# Dock_P1RB.net
KiCad netlist of a schematic drawn in EAGLE
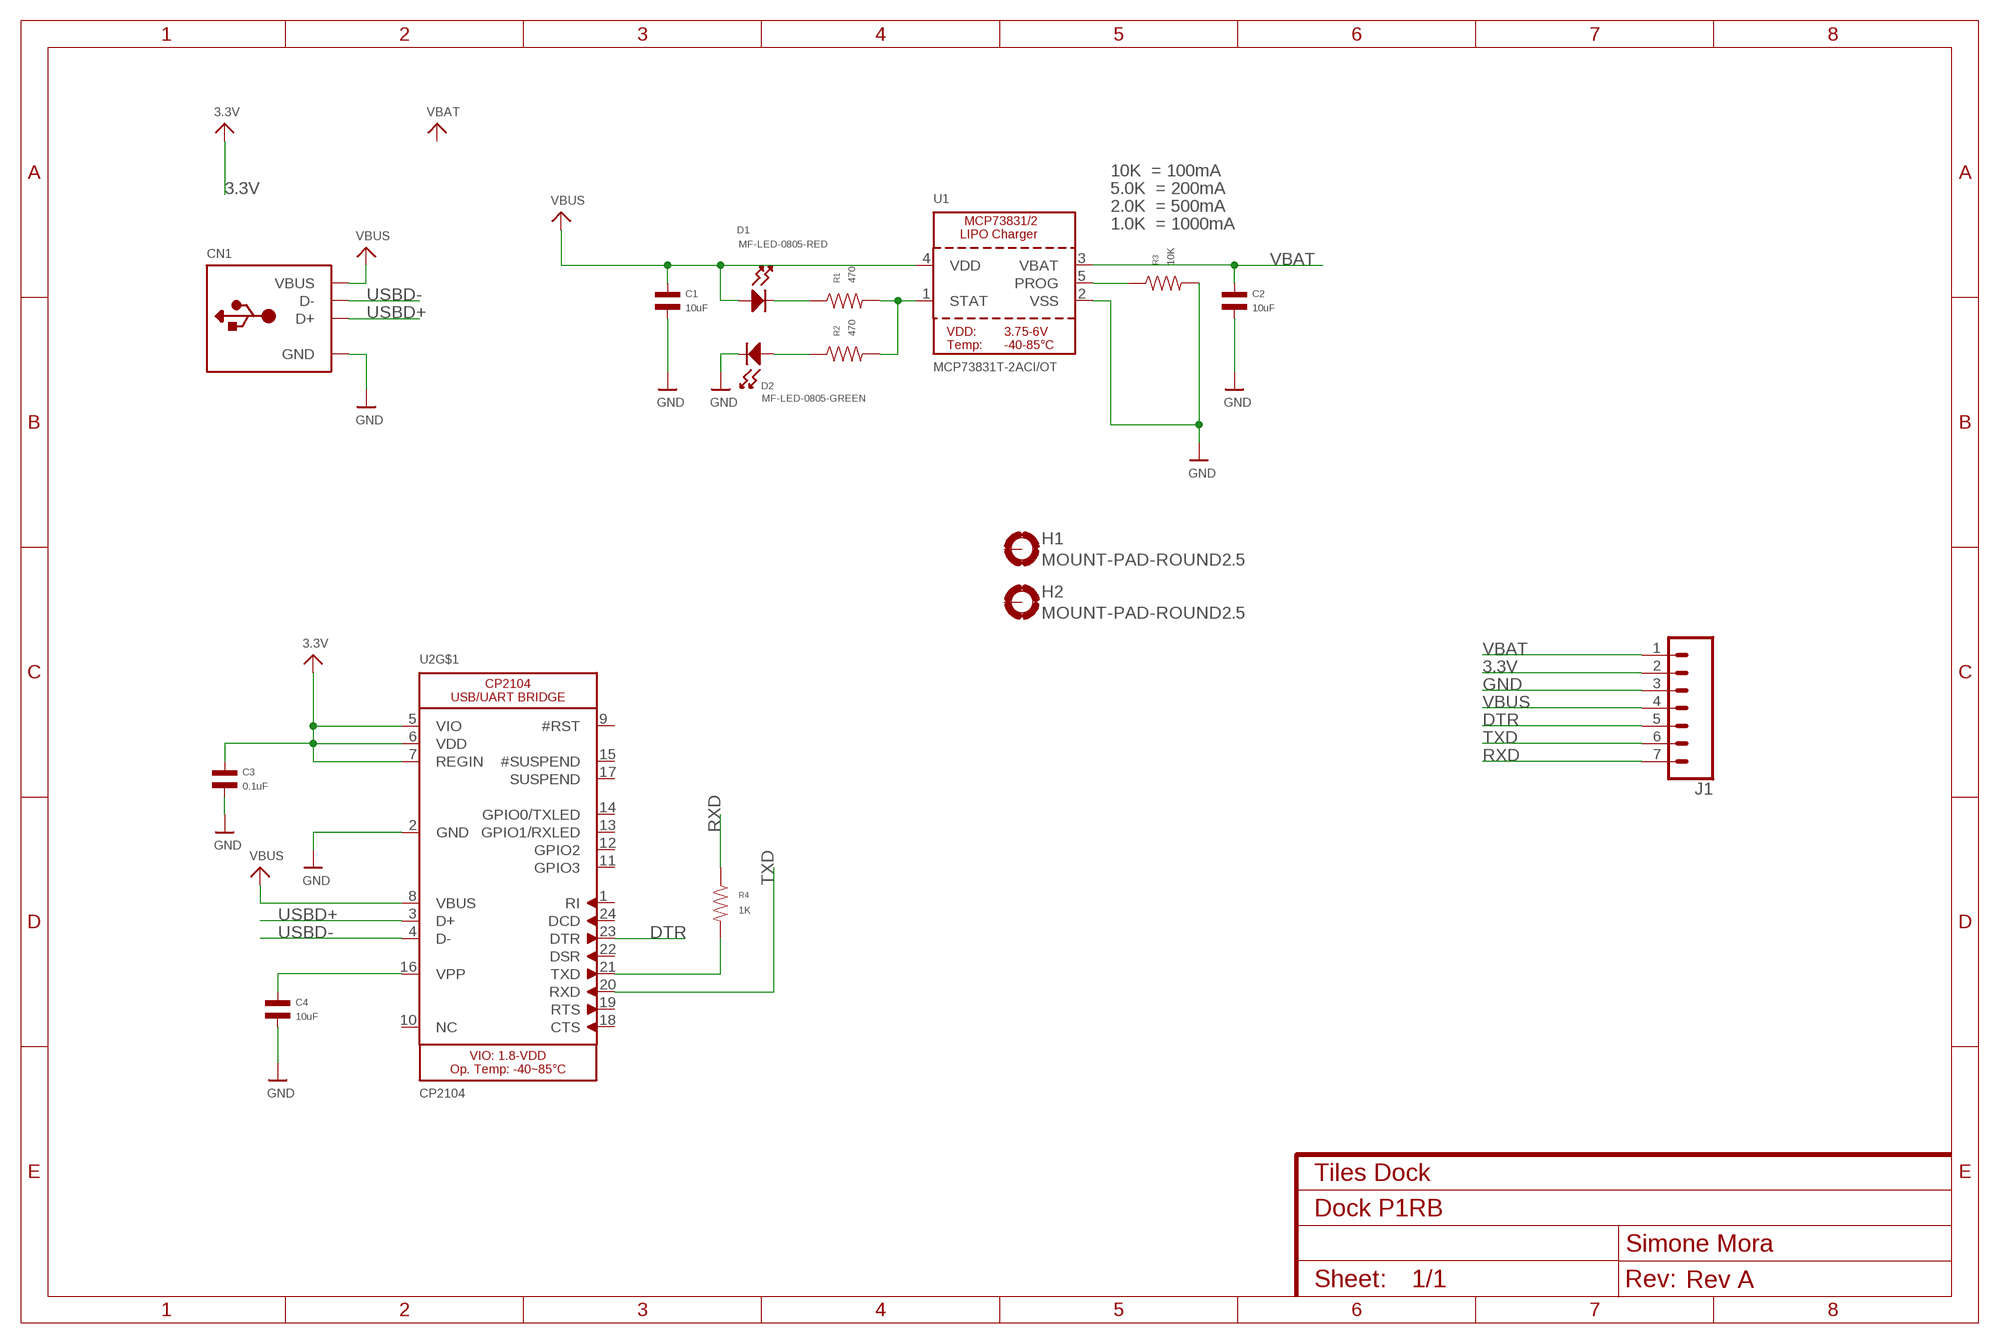
[diagram p0: schematic, sheet 1]

(export (version "E")
  (design (tool "Eeschema 10.0.6"))
  (components
    (comp (ref "C1")
      (value "10uF")
      (footprint "eagle-import:C1206")
      (fields (field (name "HOUSEPART") "YES") (field (name "MPN") "MF-CAP-1206-10uF"))
      (libsource (lib "eagle-import") (part "CAPACITOR_NP_1206"))
    )
    (comp (ref "C2")
      (value "10uF")
      (footprint "eagle-import:C1206")
      (fields (field (name "HOUSEPART") "YES") (field (name "MPN") "MF-CAP-1206-10uF"))
      (libsource (lib "eagle-import") (part "CAPACITOR_NP_1206"))
    )
    (comp (ref "C3")
      (value "0.1uF")
      (footprint "eagle-import:C0603")
      (fields (field (name "HOUSEPART") "YES") (field (name "MPN") "MF-CAP-0603-0.1uF"))
      (libsource (lib "eagle-import") (part "CAPACITOR_NP_0603"))
    )
    (comp (ref "C4")
      (value "10uF")
      (footprint "eagle-import:C1206")
      (fields (field (name "HOUSEPART") "YES") (field (name "MPN") "MF-CAP-1206-10uF"))
      (libsource (lib "eagle-import") (part "CAPACITOR_NP_1206"))
    )
    (comp (ref "CN1")
      (value "USB_TYPEAPCB")
      (footprint "eagle-import:USBA_PCB")
      (libsource (lib "eagle-import") (part "USB_TYPEAPCB"))
    )
    (comp (ref "D1")
      (value "MF-LED-0805-RED")
      (footprint "eagle-import:LED0805")
      (fields (field (name "HOUSEPART") "YES"))
      (libsource (lib "eagle-import") (part "LED_SINGLE-0805-RED"))
    )
    (comp (ref "D2")
      (value "MF-LED-0805-GREEN")
      (footprint "eagle-import:LED0805")
      (fields (field (name "HOUSEPART") "YES"))
      (libsource (lib "eagle-import") (part "LED_SINGLE-0805-GREEN"))
    )
    (comp (ref "H1")
      (value "MOUNT-PAD-ROUND2.5")
      (footprint "eagle-import:2,5-PAD-SIM")
      (libsource (lib "eagle-import") (part "MOUNT-PAD-ROUND2.5"))
    )
    (comp (ref "H2")
      (value "MOUNT-PAD-ROUND2.5")
      (footprint "eagle-import:2,5-PAD-SIM")
      (libsource (lib "eagle-import") (part "MOUNT-PAD-ROUND2.5"))
    )
    (comp (ref "J1")
      (value "CONN_07")
      (footprint "eagle-import:1X07")
      (libsource (lib "eagle-import") (part "CONN_07"))
    )
    (comp (ref "R1")
      (value "470")
      (footprint "eagle-import:R0603")
      (fields (field (name "HOUSEPART") "YES") (field (name "MPN") "MF-RES-0603-470"))
      (libsource (lib "eagle-import") (part "RESISTOR_0603"))
    )
    (comp (ref "R2")
      (value "470")
      (footprint "eagle-import:R0603")
      (fields (field (name "HOUSEPART") "YES") (field (name "MPN") "MF-RES-0603-470"))
      (libsource (lib "eagle-import") (part "RESISTOR_0603"))
    )
    (comp (ref "R3")
      (value "10K")
      (footprint "eagle-import:R0603")
      (fields (field (name "HOUSEPART") "YES") (field (name "MPN") "MF-RES-0603-10K"))
      (libsource (lib "eagle-import") (part "RESISTOR_0603"))
    )
    (comp (ref "R4")
      (value "1K")
      (footprint "eagle-import:R0603")
      (fields (field (name "HOUSEPART") "YES") (field (name "MPN") "MF-RES-0603-1K"))
      (libsource (lib "eagle-import") (part "RESISTOR_0603"))
    )
    (comp (ref "U1")
      (value "MCP73831T-2ACI/OT")
      (footprint "eagle-import:SOT23-5")
      (libsource (lib "eagle-import") (part "MCP73831/2"))
    )
    (comp (ref "U2")
      (value "CP2104")
      (footprint "eagle-import:QFN24_4MM_SMSC")
      (fields (field (name "HOUSEPART") "no"))
      (libsource (lib "eagle-import") (part "CP2104"))
    )
  )
  (nets
    (net (code "1") (name "/DTR") (class "Default")
      (node (ref "J1") (pin "5") (pinfunction "5_5") (pintype "passive"))
      (node (ref "U2") (pin "23") (pinfunction "DTR_23") (pintype "output"))
    )
    (net (code "2") (name "/RXD") (class "Default")
      (node (ref "J1") (pin "7") (pinfunction "7_7") (pintype "passive"))
      (node (ref "R4") (pin "P$1") (pinfunction "P$1_P$1") (pintype "passive"))
    )
    (net (code "3") (name "/TXD") (class "Default")
      (node (ref "J1") (pin "6") (pinfunction "6_6") (pintype "passive"))
      (node (ref "U2") (pin "20") (pinfunction "RXD_20") (pintype "input"))
    )
    (net (code "4") (name "/USBD+") (class "Default")
      (node (ref "CN1") (pin "USB_PLUS") (pinfunction "D+_USB_PLUS") (pintype "bidirectional"))
      (node (ref "U2") (pin "3") (pinfunction "D+_3") (pintype "bidirectional"))
    )
    (net (code "5") (name "/USBD-") (class "Default")
      (node (ref "CN1") (pin "USB_NEG") (pinfunction "D-_USB_NEG") (pintype "bidirectional"))
      (node (ref "U2") (pin "4") (pinfunction "D-_4") (pintype "bidirectional"))
    )
    (net (code "6") (name "3.3V") (class "Default")
      (node (ref "C3") (pin "P$1") (pinfunction "P$1_P$1") (pintype "passive"))
      (node (ref "J1") (pin "2") (pinfunction "2_2") (pintype "passive"))
      (node (ref "U2") (pin "5") (pinfunction "VIO_5") (pintype "power_in"))
      (node (ref "U2") (pin "6") (pinfunction "VDD_6") (pintype "power_in"))
      (node (ref "U2") (pin "7") (pinfunction "REGIN_7") (pintype "power_in"))
    )
    (net (code "7") (name "GND") (class "Default")
      (node (ref "C1") (pin "P$2") (pinfunction "P$2_P$2") (pintype "passive"))
      (node (ref "C2") (pin "P$2") (pinfunction "P$2_P$2") (pintype "passive"))
      (node (ref "C3") (pin "P$2") (pinfunction "P$2_P$2") (pintype "passive"))
      (node (ref "C4") (pin "P$2") (pinfunction "P$2_P$2") (pintype "passive"))
      (node (ref "CN1") (pin "GND") (pinfunction "GND_GND") (pintype "power_in"))
      (node (ref "D2") (pin "CATHODE") (pinfunction "CATHODE_CATHODE") (pintype "power_in"))
      (node (ref "J1") (pin "3") (pinfunction "3_3") (pintype "passive"))
      (node (ref "R3") (pin "P$2") (pinfunction "P$2_P$2") (pintype "passive"))
      (node (ref "U1") (pin "2") (pinfunction "VSS_2") (pintype "power_in"))
      (node (ref "U2") (pin "2") (pinfunction "GND_2") (pintype "power_in"))
    )
    (net (code "8") (name "Net-(D1-PadCATHODE)") (class "Default")
      (node (ref "D1") (pin "CATHODE") (pinfunction "CATHODE_CATHODE") (pintype "power_in"))
      (node (ref "R1") (pin "P$1") (pinfunction "P$1_P$1") (pintype "passive"))
    )
    (net (code "9") (name "Net-(D2-PadANODE)") (class "Default")
      (node (ref "D2") (pin "ANODE") (pinfunction "ANODE_ANODE") (pintype "power_in"))
      (node (ref "R2") (pin "P$1") (pinfunction "P$1_P$1") (pintype "passive"))
    )
    (net (code "10") (name "Net-(U1-PROG)") (class "Default")
      (node (ref "R3") (pin "P$1") (pinfunction "P$1_P$1") (pintype "passive"))
      (node (ref "U1") (pin "5") (pinfunction "PROG_5") (pintype "input"))
    )
    (net (code "11") (name "Net-(U1-STAT)") (class "Default")
      (node (ref "R1") (pin "P$2") (pinfunction "P$2_P$2") (pintype "passive"))
      (node (ref "R2") (pin "P$2") (pinfunction "P$2_P$2") (pintype "passive"))
      (node (ref "U1") (pin "1") (pinfunction "STAT_1") (pintype "output"))
    )
    (net (code "12") (name "Net-(U2A-TXD)") (class "Default")
      (node (ref "R4") (pin "P$2") (pinfunction "P$2_P$2") (pintype "passive"))
      (node (ref "U2") (pin "21") (pinfunction "TXD_21") (pintype "output"))
    )
    (net (code "13") (name "Net-(U2A-VPP)") (class "Default")
      (node (ref "C4") (pin "P$1") (pinfunction "P$1_P$1") (pintype "passive"))
      (node (ref "U2") (pin "16") (pinfunction "VPP_16") (pintype "bidirectional"))
    )
    (net (code "14") (name "VBAT") (class "Default")
      (node (ref "C2") (pin "P$1") (pinfunction "P$1_P$1") (pintype "passive"))
      (node (ref "J1") (pin "1") (pinfunction "1_1") (pintype "passive"))
      (node (ref "U1") (pin "3") (pinfunction "VBAT_3") (pintype "power_in"))
    )
    (net (code "15") (name "VBUS") (class "Default")
      (node (ref "C1") (pin "P$1") (pinfunction "P$1_P$1") (pintype "passive"))
      (node (ref "CN1") (pin "VCC") (pinfunction "VBUS_VCC") (pintype "power_in"))
      (node (ref "D1") (pin "ANODE") (pinfunction "ANODE_ANODE") (pintype "power_in"))
      (node (ref "J1") (pin "4") (pinfunction "4_4") (pintype "passive"))
      (node (ref "U1") (pin "4") (pinfunction "VDD_4") (pintype "power_in"))
      (node (ref "U2") (pin "8") (pinfunction "VBUS_8") (pintype "power_in"))
    )
    (net (code "16") (name "unconnected-(H1-MOUNT-PadB2,8)") (class "Default")
      (node (ref "H1") (pin "B2,8") (pinfunction "MOUNT_B2,8") (pintype "passive"))
    )
    (net (code "17") (name "unconnected-(H2-MOUNT-PadB2,8)") (class "Default")
      (node (ref "H2") (pin "B2,8") (pinfunction "MOUNT_B2,8") (pintype "passive"))
    )
    (net (code "18") (name "unconnected-(U2A-#RST-Pad9)") (class "Default")
      (node (ref "U2") (pin "9") (pinfunction "#RST_9") (pintype "bidirectional"))
    )
    (net (code "19") (name "unconnected-(U2A-#SUSPEND-Pad15)") (class "Default")
      (node (ref "U2") (pin "15") (pinfunction "#SUSPEND_15") (pintype "output"))
    )
    (net (code "20") (name "unconnected-(U2A-CTS-Pad18)") (class "Default")
      (node (ref "U2") (pin "18") (pinfunction "CTS_18") (pintype "input"))
    )
    (net (code "21") (name "unconnected-(U2A-DCD-Pad24)") (class "Default")
      (node (ref "U2") (pin "24") (pinfunction "DCD_24") (pintype "input"))
    )
    (net (code "22") (name "unconnected-(U2A-DSR-Pad22)") (class "Default")
      (node (ref "U2") (pin "22") (pinfunction "DSR_22") (pintype "input"))
    )
    (net (code "23") (name "unconnected-(U2A-GPIO0{slash}TXLED-Pad14)") (class "Default")
      (node (ref "U2") (pin "14") (pinfunction "GPIO0/TXLED_14") (pintype "bidirectional"))
    )
    (net (code "24") (name "unconnected-(U2A-GPIO1{slash}RXLED-Pad13)") (class "Default")
      (node (ref "U2") (pin "13") (pinfunction "GPIO1/RXLED_13") (pintype "bidirectional"))
    )
    (net (code "25") (name "unconnected-(U2A-GPIO2-Pad12)") (class "Default")
      (node (ref "U2") (pin "12") (pinfunction "GPIO2_12") (pintype "bidirectional"))
    )
    (net (code "26") (name "unconnected-(U2A-GPIO3-Pad11)") (class "Default")
      (node (ref "U2") (pin "11") (pinfunction "GPIO3_11") (pintype "bidirectional"))
    )
    (net (code "27") (name "unconnected-(U2A-NC-Pad10)") (class "Default")
      (node (ref "U2") (pin "10") (pinfunction "NC_10") (pintype "no_connect"))
    )
    (net (code "28") (name "unconnected-(U2A-RI-Pad1)") (class "Default")
      (node (ref "U2") (pin "1") (pinfunction "RI_1") (pintype "input"))
    )
    (net (code "29") (name "unconnected-(U2A-RTS-Pad19)") (class "Default")
      (node (ref "U2") (pin "19") (pinfunction "RTS_19") (pintype "output"))
    )
    (net (code "30") (name "unconnected-(U2A-SUSPEND-Pad17)") (class "Default")
      (node (ref "U2") (pin "17") (pinfunction "SUSPEND_17") (pintype "output"))
    )
  )
)
